# LMP2011basedV1.net
KiCad netlist of a schematic drawn in EAGLE
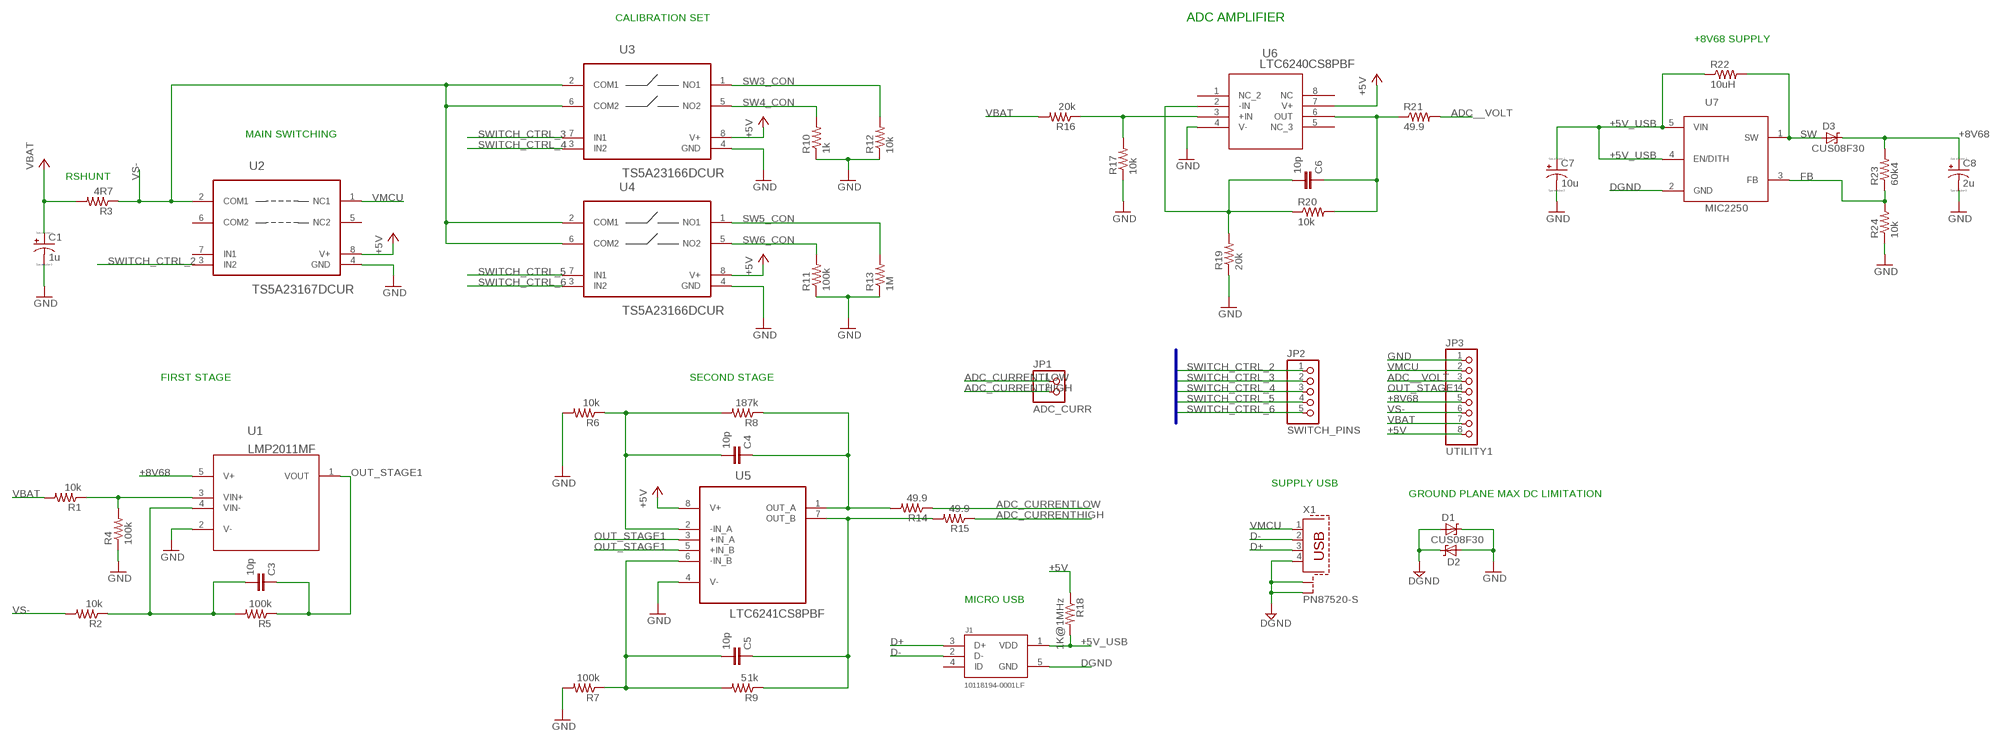
[diagram p0: schematic, sheet 1]

(export (version "E")
  (design (tool "Eeschema 10.0.6"))
  (components
    (comp (ref "C1")
      (value "1u")
      (footprint "eagle-import:PANASONIC_B")
      (libsource (lib "eagle-import") (part "CPOL-USB"))
    )
    (comp (ref "C3")
      (value "10p")
      (footprint "eagle-import:C0805")
      (libsource (lib "eagle-import") (part "C-EUC0805"))
    )
    (comp (ref "C4")
      (value "10p")
      (footprint "eagle-import:C0805")
      (libsource (lib "eagle-import") (part "C-EUC0805"))
    )
    (comp (ref "C5")
      (value "10p")
      (footprint "eagle-import:C0805")
      (libsource (lib "eagle-import") (part "C-EUC0805"))
    )
    (comp (ref "C6")
      (value "10p")
      (footprint "eagle-import:C0805")
      (libsource (lib "eagle-import") (part "C-EUC0805"))
    )
    (comp (ref "C7")
      (value "10u")
      (footprint "eagle-import:PANASONIC_B")
      (libsource (lib "eagle-import") (part "CPOL-USB"))
    )
    (comp (ref "C8")
      (value "2u")
      (footprint "eagle-import:PANASONIC_B")
      (libsource (lib "eagle-import") (part "CPOL-USB"))
    )
    (comp (ref "D1")
      (value "CUS08F30")
      (footprint "eagle-import:SOD323")
      (fields (field (name "MF") "TOSHIBA"))
      (libsource (lib "eagle-import") (part "CUS08F30"))
    )
    (comp (ref "D2")
      (value "CUS08F30")
      (footprint "eagle-import:SOD323")
      (fields (field (name "MF") "TOSHIBA"))
      (libsource (lib "eagle-import") (part "CUS08F30"))
    )
    (comp (ref "D3")
      (value "CUS08F30")
      (footprint "eagle-import:SOD323")
      (fields (field (name "MF") "TOSHIBA"))
      (libsource (lib "eagle-import") (part "CUS08F30"))
    )
    (comp (ref "J1")
      (value "10118194-0001LF")
      (footprint "eagle-import:FRAMATOME_10118194-0001LF")
      (fields (field (name "MF") "Amphenol"))
      (libsource (lib "eagle-import") (part "10118194-0001LF"))
    )
    (comp (ref "JP1")
      (value "ADC_CURR")
      (footprint "eagle-import:1X02")
      (libsource (lib "eagle-import") (part "PINHD-1X2"))
    )
    (comp (ref "JP2")
      (value "SWITCH_PINS")
      (footprint "eagle-import:1X05")
      (libsource (lib "eagle-import") (part "PINHD-1X5"))
    )
    (comp (ref "JP3")
      (value "UTILITY1")
      (footprint "eagle-import:1X08")
      (libsource (lib "eagle-import") (part "PINHD-1X8"))
    )
    (comp (ref "R1")
      (value "10k")
      (footprint "eagle-import:R0805")
      (libsource (lib "eagle-import") (part "R-US_R0805"))
    )
    (comp (ref "R2")
      (value "10k")
      (footprint "eagle-import:R0805")
      (libsource (lib "eagle-import") (part "R-US_R0805"))
    )
    (comp (ref "R3")
      (value "4R7")
      (footprint "eagle-import:R0805")
      (libsource (lib "eagle-import") (part "R-US_R0805"))
    )
    (comp (ref "R4")
      (value "100k")
      (footprint "eagle-import:R0805")
      (libsource (lib "eagle-import") (part "R-US_R0805"))
    )
    (comp (ref "R5")
      (value "100k")
      (footprint "eagle-import:R0805")
      (libsource (lib "eagle-import") (part "R-US_R0805"))
    )
    (comp (ref "R6")
      (value "10k")
      (footprint "eagle-import:R0805")
      (libsource (lib "eagle-import") (part "R-US_R0805"))
    )
    (comp (ref "R7")
      (value "100k")
      (footprint "eagle-import:R0805")
      (libsource (lib "eagle-import") (part "R-US_R0805"))
    )
    (comp (ref "R8")
      (value "187k")
      (footprint "eagle-import:R0805")
      (libsource (lib "eagle-import") (part "R-US_R0805"))
    )
    (comp (ref "R9")
      (value "51k")
      (footprint "eagle-import:R0805")
      (libsource (lib "eagle-import") (part "R-US_R0805"))
    )
    (comp (ref "R10")
      (value "1k")
      (footprint "eagle-import:R0805")
      (libsource (lib "eagle-import") (part "R-US_R0805"))
    )
    (comp (ref "R11")
      (value "100k")
      (footprint "eagle-import:R0805")
      (libsource (lib "eagle-import") (part "R-US_R0805"))
    )
    (comp (ref "R12")
      (value "10k")
      (footprint "eagle-import:R0805")
      (libsource (lib "eagle-import") (part "R-US_R0805"))
    )
    (comp (ref "R13")
      (value "1M")
      (footprint "eagle-import:R0805")
      (libsource (lib "eagle-import") (part "R-US_R0805"))
    )
    (comp (ref "R14")
      (value "49.9")
      (footprint "eagle-import:R0805")
      (libsource (lib "eagle-import") (part "R-US_R0805"))
    )
    (comp (ref "R15")
      (value "49.9")
      (footprint "eagle-import:R0805")
      (libsource (lib "eagle-import") (part "R-US_R0805"))
    )
    (comp (ref "R16")
      (value "20k")
      (footprint "eagle-import:R0805")
      (libsource (lib "eagle-import") (part "R-US_R0805"))
    )
    (comp (ref "R17")
      (value "10k")
      (footprint "eagle-import:R0805")
      (libsource (lib "eagle-import") (part "R-US_R0805"))
    )
    (comp (ref "R18")
      (value "1K@1MHz")
      (footprint "eagle-import:R0805")
      (libsource (lib "eagle-import") (part "R-US_R0805"))
    )
    (comp (ref "R19")
      (value "20k")
      (footprint "eagle-import:R0805")
      (libsource (lib "eagle-import") (part "R-US_R0805"))
    )
    (comp (ref "R20")
      (value "10k")
      (footprint "eagle-import:R0805")
      (libsource (lib "eagle-import") (part "R-US_R0805"))
    )
    (comp (ref "R21")
      (value "49.9")
      (footprint "eagle-import:R0603")
      (libsource (lib "eagle-import") (part "R-US_R0603"))
    )
    (comp (ref "R22")
      (value "10uH")
      (footprint "eagle-import:R1210")
      (libsource (lib "eagle-import") (part "R-US_R1210"))
    )
    (comp (ref "R23")
      (value "60k4")
      (footprint "eagle-import:R0805")
      (libsource (lib "eagle-import") (part "R-US_R0805"))
    )
    (comp (ref "R24")
      (value "10k")
      (footprint "eagle-import:R0805")
      (libsource (lib "eagle-import") (part "R-US_R0805"))
    )
    (comp (ref "U1")
      (value "LMP2011MF")
      (footprint "eagle-import:SOT95P285X120-5N")
      (fields
        (field (name "DIGI-KEY_PART_NUMBER") "LMP2011MF/NOPBCT-ND")
        (field (name "MF") "Texas Instruments")
        (field (name "MP") "LMP2011MF/NOPB")
      )
      (libsource (lib "eagle-import") (part "LMP2011MF"))
    )
    (comp (ref "U2")
      (value "TS5A23167DCUR")
      (footprint "eagle-import:SOP50P310X90-8N")
      (fields (field (name "MF") "Texas Instruments"))
      (libsource (lib "eagle-import") (part "TS5A23167DCUR"))
    )
    (comp (ref "U3")
      (value "TS5A23166DCUR")
      (footprint "eagle-import:SOP50P310X90-8N")
      (fields (field (name "MF") "Texas Instruments"))
      (libsource (lib "eagle-import") (part "TS5A23166DCUR"))
    )
    (comp (ref "U4")
      (value "TS5A23166DCUR")
      (footprint "eagle-import:SOP50P310X90-8N")
      (fields (field (name "MF") "Texas Instruments"))
      (libsource (lib "eagle-import") (part "TS5A23166DCUR"))
    )
    (comp (ref "U5")
      (value "LTC6241CS8PBF")
      (footprint "eagle-import:SOIC127P600X175-8N")
      (fields (field (name "MF") "Linear Technology") (field (name "MP") "LTC6241CS8#PBF"))
      (libsource (lib "eagle-import") (part "LTC6241CS8PBF"))
    )
    (comp (ref "U6")
      (value "LTC6240CS8PBF")
      (footprint "eagle-import:SO-8_S")
      (fields (field (name "MF") "Linear Technology") (field (name "MP") "LTC6240CS8#PBF"))
      (libsource (lib "eagle-import") (part "LTC6240CS8PBF"))
    )
    (comp (ref "U7")
      (value "MIC2250")
      (footprint "eagle-import:SOT95P270X145-5N")
      (fields (field (name "MF") "MICROCHIP"))
      (libsource (lib "eagle-import") (part "MIC2250"))
    )
    (comp (ref "X1")
      (value "PN87520-S")
      (footprint "eagle-import:PN87520-S")
      (libsource (lib "eagle-import") (part "PN87520-S"))
    )
  )
  (nets
    (net (code "1") (name "+5V") (class "Default")
      (node (ref "JP3") (pin "8") (pinfunction "8_8") (pintype "passive"))
      (node (ref "R18") (pin "1") (pinfunction "1_1") (pintype "passive"))
      (node (ref "U2") (pin "8") (pinfunction "V+_8") (pintype "power_in"))
      (node (ref "U3") (pin "8") (pinfunction "V+_8") (pintype "power_in"))
      (node (ref "U4") (pin "8") (pinfunction "V+_8") (pintype "power_in"))
      (node (ref "U5") (pin "8") (pinfunction "V+_8") (pintype "power_in"))
      (node (ref "U6") (pin "7") (pinfunction "V+_7") (pintype "power_in"))
    )
    (net (code "2") (name "/+5V_USB") (class "Default")
      (node (ref "C7") (pin "+") (pinfunction "+_+") (pintype "passive"))
      (node (ref "J1") (pin "1") (pinfunction "VDD_1") (pintype "power_in"))
      (node (ref "R18") (pin "2") (pinfunction "2_2") (pintype "passive"))
      (node (ref "R22") (pin "1") (pinfunction "1_1") (pintype "passive"))
      (node (ref "U7") (pin "4") (pinfunction "EN/DITH_4") (pintype "bidirectional"))
      (node (ref "U7") (pin "5") (pinfunction "VIN_5") (pintype "bidirectional"))
    )
    (net (code "3") (name "/+8V68") (class "Default")
      (node (ref "C8") (pin "+") (pinfunction "+_+") (pintype "passive"))
      (node (ref "D3") (pin "C") (pinfunction "C_C") (pintype "passive"))
      (node (ref "JP3") (pin "5") (pinfunction "5_5") (pintype "passive"))
      (node (ref "R23") (pin "2") (pinfunction "2_2") (pintype "passive"))
      (node (ref "U1") (pin "5") (pinfunction "V+_5") (pintype "power_in"))
    )
    (net (code "4") (name "/ADC_CURRENTHIGH") (class "Default")
      (node (ref "JP1") (pin "2") (pinfunction "2_2") (pintype "passive"))
      (node (ref "R15") (pin "1") (pinfunction "1_1") (pintype "passive"))
    )
    (net (code "5") (name "/ADC_CURRENTLOW") (class "Default")
      (node (ref "JP1") (pin "1") (pinfunction "1_1") (pintype "passive"))
      (node (ref "R14") (pin "1") (pinfunction "1_1") (pintype "passive"))
    )
    (net (code "6") (name "/ADC__VOLT") (class "Default")
      (node (ref "JP3") (pin "3") (pinfunction "3_3") (pintype "passive"))
      (node (ref "R21") (pin "2") (pinfunction "2_2") (pintype "passive"))
    )
    (net (code "7") (name "/D+") (class "Default")
      (node (ref "J1") (pin "3") (pinfunction "D+_3") (pintype "bidirectional"))
      (node (ref "X1") (pin "3") (pinfunction "3_3") (pintype "passive"))
    )
    (net (code "8") (name "/D-") (class "Default")
      (node (ref "J1") (pin "2") (pinfunction "D-_2") (pintype "bidirectional"))
      (node (ref "X1") (pin "2") (pinfunction "2_2") (pintype "passive"))
    )
    (net (code "9") (name "/FB") (class "Default")
      (node (ref "R23") (pin "1") (pinfunction "1_1") (pintype "passive"))
      (node (ref "R24") (pin "2") (pinfunction "2_2") (pintype "passive"))
      (node (ref "U7") (pin "3") (pinfunction "FB_3") (pintype "bidirectional"))
    )
    (net (code "10") (name "/OUT_STAGE1") (class "Default")
      (node (ref "C3") (pin "1") (pinfunction "1_1") (pintype "passive"))
      (node (ref "JP3") (pin "4") (pinfunction "4_4") (pintype "passive"))
      (node (ref "R5") (pin "1") (pinfunction "1_1") (pintype "passive"))
      (node (ref "U1") (pin "1") (pinfunction "VOUT_1") (pintype "output"))
      (node (ref "U5") (pin "3") (pinfunction "+IN_A_3") (pintype "input"))
      (node (ref "U5") (pin "5") (pinfunction "+IN_B_5") (pintype "input"))
    )
    (net (code "11") (name "/SW") (class "Default")
      (node (ref "D3") (pin "A") (pinfunction "A_A") (pintype "passive"))
      (node (ref "R22") (pin "2") (pinfunction "2_2") (pintype "passive"))
      (node (ref "U7") (pin "1") (pinfunction "SW_1") (pintype "bidirectional"))
    )
    (net (code "12") (name "/SW3_CON") (class "Default")
      (node (ref "R12") (pin "2") (pinfunction "2_2") (pintype "passive"))
      (node (ref "U3") (pin "1") (pinfunction "NO1_1") (pintype "bidirectional"))
    )
    (net (code "13") (name "/SW4_CON") (class "Default")
      (node (ref "R10") (pin "2") (pinfunction "2_2") (pintype "passive"))
      (node (ref "U3") (pin "5") (pinfunction "NO2_5") (pintype "bidirectional"))
    )
    (net (code "14") (name "/SW5_CON") (class "Default")
      (node (ref "R13") (pin "2") (pinfunction "2_2") (pintype "passive"))
      (node (ref "U4") (pin "1") (pinfunction "NO1_1") (pintype "bidirectional"))
    )
    (net (code "15") (name "/SW6_CON") (class "Default")
      (node (ref "R11") (pin "2") (pinfunction "2_2") (pintype "passive"))
      (node (ref "U4") (pin "5") (pinfunction "NO2_5") (pintype "bidirectional"))
    )
    (net (code "16") (name "/SWITCH_CTRL_2") (class "Default")
      (node (ref "JP2") (pin "1") (pinfunction "1_1") (pintype "passive"))
      (node (ref "U2") (pin "3") (pinfunction "IN2_3") (pintype "input"))
    )
    (net (code "17") (name "/SWITCH_CTRL_3") (class "Default")
      (node (ref "JP2") (pin "2") (pinfunction "2_2") (pintype "passive"))
      (node (ref "U3") (pin "7") (pinfunction "IN1_7") (pintype "input"))
    )
    (net (code "18") (name "/SWITCH_CTRL_4") (class "Default")
      (node (ref "JP2") (pin "3") (pinfunction "3_3") (pintype "passive"))
      (node (ref "U3") (pin "3") (pinfunction "IN2_3") (pintype "input"))
    )
    (net (code "19") (name "/SWITCH_CTRL_5") (class "Default")
      (node (ref "JP2") (pin "4") (pinfunction "4_4") (pintype "passive"))
      (node (ref "U4") (pin "7") (pinfunction "IN1_7") (pintype "input"))
    )
    (net (code "20") (name "/SWITCH_CTRL_6") (class "Default")
      (node (ref "JP2") (pin "5") (pinfunction "5_5") (pintype "passive"))
      (node (ref "U4") (pin "3") (pinfunction "IN2_3") (pintype "input"))
    )
    (net (code "21") (name "/VMCU") (class "Default")
      (node (ref "JP3") (pin "2") (pinfunction "2_2") (pintype "passive"))
      (node (ref "U2") (pin "1") (pinfunction "NC1_1") (pintype "bidirectional"))
      (node (ref "X1") (pin "1") (pinfunction "1_1") (pintype "passive"))
    )
    (net (code "22") (name "/VS-") (class "Default")
      (node (ref "JP3") (pin "6") (pinfunction "6_6") (pintype "passive"))
      (node (ref "R2") (pin "2") (pinfunction "2_2") (pintype "passive"))
      (node (ref "R3") (pin "1") (pinfunction "1_1") (pintype "passive"))
      (node (ref "U2") (pin "2") (pinfunction "COM1_2") (pintype "bidirectional"))
      (node (ref "U3") (pin "2") (pinfunction "COM1_2") (pintype "bidirectional"))
      (node (ref "U3") (pin "6") (pinfunction "COM2_6") (pintype "bidirectional"))
      (node (ref "U4") (pin "2") (pinfunction "COM1_2") (pintype "bidirectional"))
      (node (ref "U4") (pin "6") (pinfunction "COM2_6") (pintype "bidirectional"))
    )
    (net (code "23") (name "DGND") (class "Default")
      (node (ref "D1") (pin "A") (pinfunction "A_A") (pintype "passive"))
      (node (ref "D2") (pin "C") (pinfunction "C_C") (pintype "passive"))
      (node (ref "J1") (pin "5") (pinfunction "GND_5") (pintype "power_in"))
      (node (ref "U7") (pin "2") (pinfunction "GND_2") (pintype "bidirectional"))
      (node (ref "X1") (pin "4") (pinfunction "4_4") (pintype "passive"))
      (node (ref "X1") (pin "S1") (pinfunction "S1_S1") (pintype "passive"))
      (node (ref "X1") (pin "S2") (pinfunction "S2_S2") (pintype "passive"))
    )
    (net (code "24") (name "GND") (class "Default")
      (node (ref "C1") (pin "-") (pinfunction "-_-") (pintype "passive"))
      (node (ref "C7") (pin "-") (pinfunction "-_-") (pintype "passive"))
      (node (ref "C8") (pin "-") (pinfunction "-_-") (pintype "passive"))
      (node (ref "D1") (pin "C") (pinfunction "C_C") (pintype "passive"))
      (node (ref "D2") (pin "A") (pinfunction "A_A") (pintype "passive"))
      (node (ref "JP3") (pin "1") (pinfunction "1_1") (pintype "passive"))
      (node (ref "R10") (pin "1") (pinfunction "1_1") (pintype "passive"))
      (node (ref "R11") (pin "1") (pinfunction "1_1") (pintype "passive"))
      (node (ref "R12") (pin "1") (pinfunction "1_1") (pintype "passive"))
      (node (ref "R13") (pin "1") (pinfunction "1_1") (pintype "passive"))
      (node (ref "R17") (pin "1") (pinfunction "1_1") (pintype "passive"))
      (node (ref "R19") (pin "1") (pinfunction "1_1") (pintype "passive"))
      (node (ref "R24") (pin "1") (pinfunction "1_1") (pintype "passive"))
      (node (ref "R4") (pin "1") (pinfunction "1_1") (pintype "passive"))
      (node (ref "R6") (pin "2") (pinfunction "2_2") (pintype "passive"))
      (node (ref "R7") (pin "2") (pinfunction "2_2") (pintype "passive"))
      (node (ref "U1") (pin "2") (pinfunction "V-_2") (pintype "power_in"))
      (node (ref "U2") (pin "4") (pinfunction "GND_4") (pintype "passive"))
      (node (ref "U3") (pin "4") (pinfunction "GND_4") (pintype "passive"))
      (node (ref "U4") (pin "4") (pinfunction "GND_4") (pintype "passive"))
      (node (ref "U5") (pin "4") (pinfunction "V-_4") (pintype "power_in"))
      (node (ref "U6") (pin "4") (pinfunction "V-_4") (pintype "power_in"))
    )
    (net (code "25") (name "Net-(U1-VIN+)") (class "Default")
      (node (ref "R1") (pin "1") (pinfunction "1_1") (pintype "passive"))
      (node (ref "R4") (pin "2") (pinfunction "2_2") (pintype "passive"))
      (node (ref "U1") (pin "3") (pinfunction "VIN+_3") (pintype "input"))
    )
    (net (code "26") (name "Net-(U1-VIN-)") (class "Default")
      (node (ref "C3") (pin "2") (pinfunction "2_2") (pintype "passive"))
      (node (ref "R2") (pin "1") (pinfunction "1_1") (pintype "passive"))
      (node (ref "R5") (pin "2") (pinfunction "2_2") (pintype "passive"))
      (node (ref "U1") (pin "4") (pinfunction "VIN-_4") (pintype "input"))
    )
    (net (code "27") (name "Net-(U5--IN_A)") (class "Default")
      (node (ref "C4") (pin "2") (pinfunction "2_2") (pintype "passive"))
      (node (ref "R6") (pin "1") (pinfunction "1_1") (pintype "passive"))
      (node (ref "R8") (pin "2") (pinfunction "2_2") (pintype "passive"))
      (node (ref "U5") (pin "2") (pinfunction "-IN_A_2") (pintype "input"))
    )
    (net (code "28") (name "Net-(U5--IN_B)") (class "Default")
      (node (ref "C5") (pin "2") (pinfunction "2_2") (pintype "passive"))
      (node (ref "R7") (pin "1") (pinfunction "1_1") (pintype "passive"))
      (node (ref "R9") (pin "2") (pinfunction "2_2") (pintype "passive"))
      (node (ref "U5") (pin "6") (pinfunction "-IN_B_6") (pintype "input"))
    )
    (net (code "29") (name "Net-(U5-OUT_A)") (class "Default")
      (node (ref "C4") (pin "1") (pinfunction "1_1") (pintype "passive"))
      (node (ref "R14") (pin "2") (pinfunction "2_2") (pintype "passive"))
      (node (ref "R8") (pin "1") (pinfunction "1_1") (pintype "passive"))
      (node (ref "U5") (pin "1") (pinfunction "OUT_A_1") (pintype "output"))
    )
    (net (code "30") (name "Net-(U5-OUT_B)") (class "Default")
      (node (ref "C5") (pin "1") (pinfunction "1_1") (pintype "passive"))
      (node (ref "R15") (pin "2") (pinfunction "2_2") (pintype "passive"))
      (node (ref "R9") (pin "1") (pinfunction "1_1") (pintype "passive"))
      (node (ref "U5") (pin "7") (pinfunction "OUT_B_7") (pintype "output"))
    )
    (net (code "31") (name "Net-(U6-+IN)") (class "Default")
      (node (ref "R16") (pin "1") (pinfunction "1_1") (pintype "passive"))
      (node (ref "R17") (pin "2") (pinfunction "2_2") (pintype "passive"))
      (node (ref "U6") (pin "3") (pinfunction "+IN_3") (pintype "input"))
    )
    (net (code "32") (name "Net-(U6--IN)") (class "Default")
      (node (ref "C6") (pin "2") (pinfunction "2_2") (pintype "passive"))
      (node (ref "R19") (pin "2") (pinfunction "2_2") (pintype "passive"))
      (node (ref "R20") (pin "1") (pinfunction "1_1") (pintype "passive"))
      (node (ref "U6") (pin "2") (pinfunction "-IN_2") (pintype "input"))
    )
    (net (code "33") (name "Net-(U6-OUT)") (class "Default")
      (node (ref "C6") (pin "1") (pinfunction "1_1") (pintype "passive"))
      (node (ref "R20") (pin "2") (pinfunction "2_2") (pintype "passive"))
      (node (ref "R21") (pin "1") (pinfunction "1_1") (pintype "passive"))
      (node (ref "U6") (pin "6") (pinfunction "OUT_6") (pintype "output"))
    )
    (net (code "34") (name "VBAT") (class "Default")
      (node (ref "C1") (pin "+") (pinfunction "+_+") (pintype "passive"))
      (node (ref "JP3") (pin "7") (pinfunction "7_7") (pintype "passive"))
      (node (ref "R1") (pin "2") (pinfunction "2_2") (pintype "passive"))
      (node (ref "R16") (pin "2") (pinfunction "2_2") (pintype "passive"))
      (node (ref "R3") (pin "2") (pinfunction "2_2") (pintype "passive"))
    )
    (net (code "35") (name "unconnected-(J1-ID-Pad4)") (class "Default")
      (node (ref "J1") (pin "4") (pinfunction "ID_4") (pintype "passive"))
    )
    (net (code "36") (name "unconnected-(U2-COM2-Pad6)") (class "Default")
      (node (ref "U2") (pin "6") (pinfunction "COM2_6") (pintype "bidirectional"))
    )
    (net (code "37") (name "unconnected-(U2-IN1-Pad7)") (class "Default")
      (node (ref "U2") (pin "7") (pinfunction "IN1_7") (pintype "input"))
    )
    (net (code "38") (name "unconnected-(U2-NC2-Pad5)") (class "Default")
      (node (ref "U2") (pin "5") (pinfunction "NC2_5") (pintype "bidirectional"))
    )
    (net (code "39") (name "unconnected-(U6-NC-Pad8)") (class "Default")
      (node (ref "U6") (pin "8") (pinfunction "NC_8") (pintype "no_connect"))
    )
    (net (code "40") (name "unconnected-(U6-NC_2-Pad1)") (class "Default")
      (node (ref "U6") (pin "1") (pinfunction "NC_2_1") (pintype "no_connect"))
    )
    (net (code "41") (name "unconnected-(U6-NC_3-Pad5)") (class "Default")
      (node (ref "U6") (pin "5") (pinfunction "NC_3_5") (pintype "no_connect"))
    )
  )
)
